# STM32_DDS.net
KiCad netlist of a schematic drawn in Altium Designer
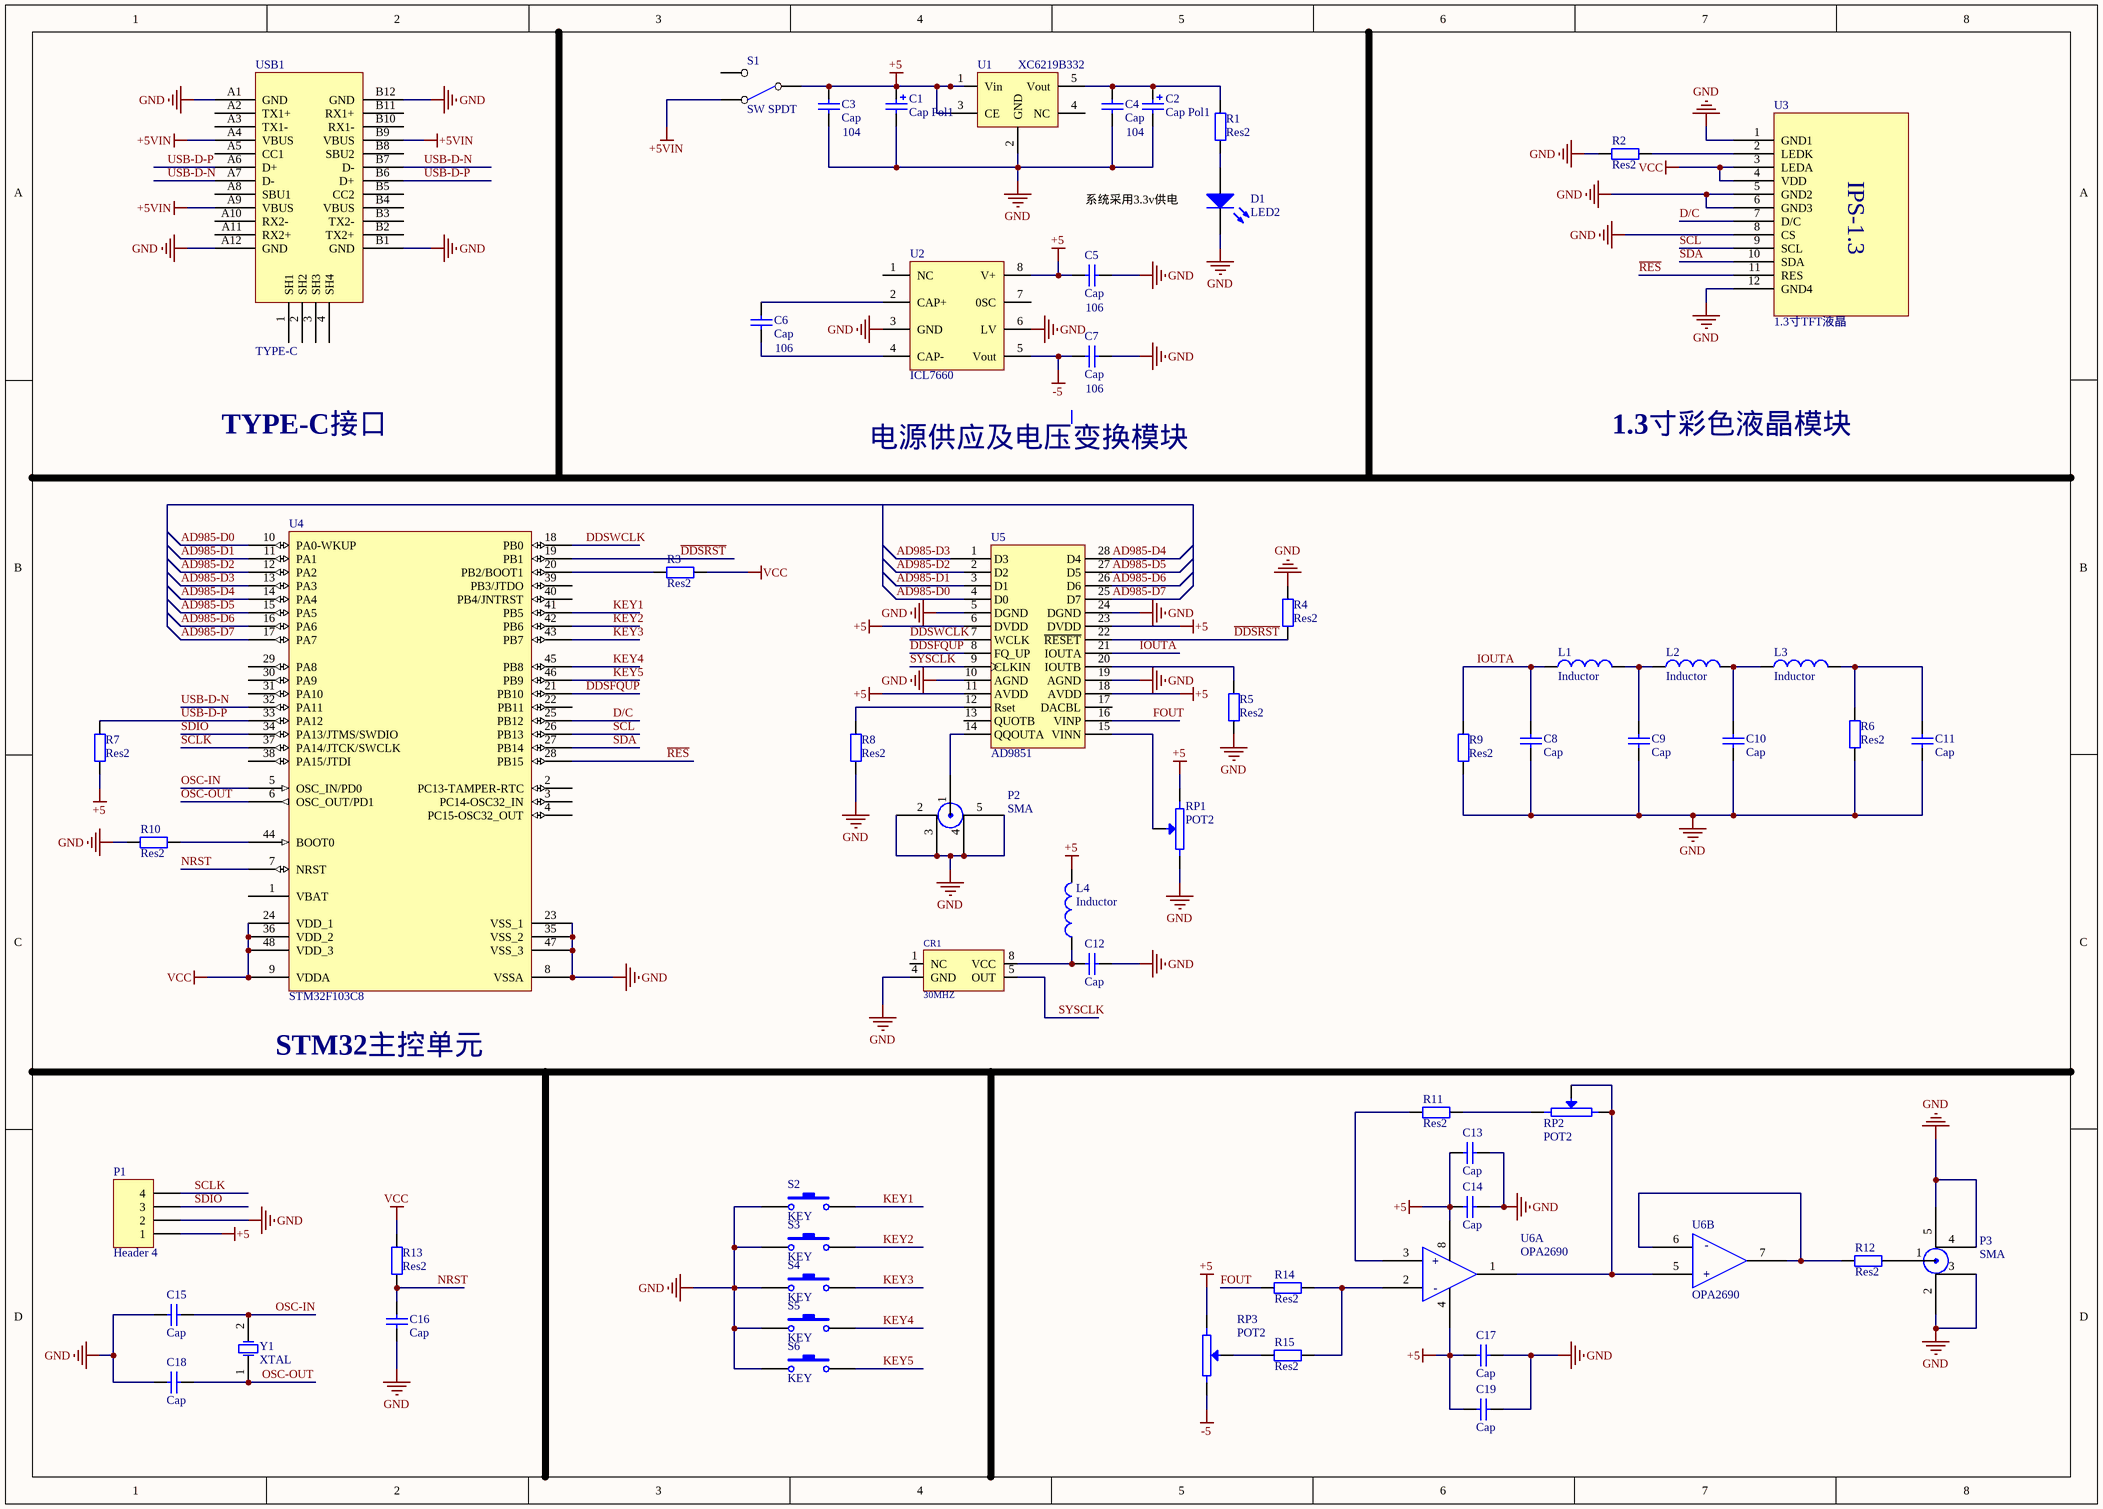
[diagram p0: 基于STM32的DDS信号源的设计实例.SchDoc]

(export (version "E")
  (design (tool "Eeschema 10.0.6"))
  (components
    (comp (ref "C1")
      (value "Cap Pol1")
      (footprint "C1210_N")
      (description "Polarized Capacitor (Radial)")
      (fields (field (name "PUBLISHER") "Altium Limited"))
      (libsource (lib "基于STM32的DDS信号源设计实例") (part "Cap Pol1"))
    )
    (comp (ref "C2")
      (value "Cap Pol1")
      (footprint "C1210_N")
      (description "Polarized Capacitor (Radial)")
      (fields (field (name "PUBLISHER") "Altium Limited"))
      (libsource (lib "基于STM32的DDS信号源设计实例") (part "Cap Pol1"))
    )
    (comp (ref "C3")
      (value "Cap")
      (footprint "C0805")
      (description "Capacitor")
      (fields (field (name "ALTIUM_VALUE") "104") (field (name "PUBLISHER") "Altium Limited"))
      (libsource (lib "基于STM32的DDS信号源设计实例") (part "Cap"))
    )
    (comp (ref "C4")
      (value "Cap")
      (footprint "C0805")
      (description "Capacitor")
      (fields (field (name "ALTIUM_VALUE") "104") (field (name "PUBLISHER") "Altium Limited"))
      (libsource (lib "基于STM32的DDS信号源设计实例") (part "Cap"))
    )
    (comp (ref "C5")
      (value "Cap")
      (footprint "C0805")
      (description "Capacitor")
      (fields (field (name "ALTIUM_VALUE") "106") (field (name "PUBLISHER") "Altium Limited"))
      (libsource (lib "基于STM32的DDS信号源设计实例") (part "Cap"))
    )
    (comp (ref "C6")
      (value "Cap")
      (footprint "C0805")
      (description "Capacitor")
      (fields (field (name "ALTIUM_VALUE") "106") (field (name "PUBLISHER") "Altium Limited"))
      (libsource (lib "基于STM32的DDS信号源设计实例") (part "Cap"))
    )
    (comp (ref "C7")
      (value "Cap")
      (footprint "C0805")
      (description "Capacitor")
      (fields (field (name "ALTIUM_VALUE") "106") (field (name "PUBLISHER") "Altium Limited"))
      (libsource (lib "基于STM32的DDS信号源设计实例") (part "Cap"))
    )
    (comp (ref "C8")
      (value "Cap")
      (footprint "C0805")
      (description "Capacitor")
      (fields (field (name "PUBLISHER") "Altium Limited"))
      (libsource (lib "基于STM32的DDS信号源设计实例") (part "Cap"))
    )
    (comp (ref "C9")
      (value "Cap")
      (footprint "C0805")
      (description "Capacitor")
      (fields (field (name "PUBLISHER") "Altium Limited"))
      (libsource (lib "基于STM32的DDS信号源设计实例") (part "Cap"))
    )
    (comp (ref "C10")
      (value "Cap")
      (footprint "C0805")
      (description "Capacitor")
      (fields (field (name "PUBLISHER") "Altium Limited"))
      (libsource (lib "基于STM32的DDS信号源设计实例") (part "Cap"))
    )
    (comp (ref "C11")
      (value "Cap")
      (footprint "C0805")
      (description "Capacitor")
      (fields (field (name "PUBLISHER") "Altium Limited"))
      (libsource (lib "基于STM32的DDS信号源设计实例") (part "Cap"))
    )
    (comp (ref "C12")
      (value "Cap")
      (footprint "C0805")
      (description "Capacitor")
      (fields (field (name "PUBLISHER") "Altium Limited"))
      (libsource (lib "基于STM32的DDS信号源设计实例") (part "Cap"))
    )
    (comp (ref "C13")
      (value "Cap")
      (footprint "C0805")
      (description "Capacitor")
      (fields (field (name "PUBLISHER") "Altium Limited"))
      (libsource (lib "基于STM32的DDS信号源设计实例") (part "Cap"))
    )
    (comp (ref "C14")
      (value "Cap")
      (footprint "C0805")
      (description "Capacitor")
      (fields (field (name "PUBLISHER") "Altium Limited"))
      (libsource (lib "基于STM32的DDS信号源设计实例") (part "Cap"))
    )
    (comp (ref "C15")
      (value "Cap")
      (footprint "C0805")
      (description "Capacitor")
      (fields (field (name "PUBLISHER") "Altium Limited"))
      (libsource (lib "基于STM32的DDS信号源设计实例") (part "Cap"))
    )
    (comp (ref "C16")
      (value "Cap")
      (footprint "C0805")
      (description "Capacitor")
      (fields (field (name "PUBLISHER") "Altium Limited"))
      (libsource (lib "基于STM32的DDS信号源设计实例") (part "Cap"))
    )
    (comp (ref "C17")
      (value "Cap")
      (footprint "C0805")
      (description "Capacitor")
      (fields (field (name "PUBLISHER") "Altium Limited"))
      (libsource (lib "基于STM32的DDS信号源设计实例") (part "Cap"))
    )
    (comp (ref "C18")
      (value "Cap")
      (footprint "C0805")
      (description "Capacitor")
      (fields (field (name "PUBLISHER") "Altium Limited"))
      (libsource (lib "基于STM32的DDS信号源设计实例") (part "Cap"))
    )
    (comp (ref "C19")
      (value "Cap")
      (footprint "C0805")
      (description "Capacitor")
      (fields (field (name "PUBLISHER") "Altium Limited"))
      (libsource (lib "基于STM32的DDS信号源设计实例") (part "Cap"))
    )
    (comp (ref "CR1")
      (value "30MHZ")
      (footprint "CRYSTAL-SMT-5X7")
      (libsource (lib "基于STM32的DDS信号源设计实例") (part "CRYSTAL-DIP8"))
    )
    (comp (ref "D1")
      (value "LED2")
      (footprint "D0805+")
      (description "Typical RED, GREEN, YELLOW, AMBER GaAs LED")
      (fields (field (name "PUBLISHER") "Altium Limited"))
      (libsource (lib "基于STM32的DDS信号源设计实例") (part "LED2"))
    )
    (comp (ref "L1")
      (value "Inductor")
      (footprint "6-0805_N")
      (fields (field (name "PUBLISHER") "Altium Limited"))
      (libsource (lib "基于STM32的DDS信号源设计实例") (part "Inductor"))
    )
    (comp (ref "L2")
      (value "Inductor")
      (footprint "6-0805_N")
      (fields (field (name "PUBLISHER") "Altium Limited"))
      (libsource (lib "基于STM32的DDS信号源设计实例") (part "Inductor"))
    )
    (comp (ref "L3")
      (value "Inductor")
      (footprint "6-0805_N")
      (fields (field (name "PUBLISHER") "Altium Limited"))
      (libsource (lib "基于STM32的DDS信号源设计实例") (part "Inductor"))
    )
    (comp (ref "L4")
      (value "Inductor")
      (footprint "6-0805_N")
      (fields (field (name "PUBLISHER") "Altium Limited"))
      (libsource (lib "基于STM32的DDS信号源设计实例") (part "Inductor"))
    )
    (comp (ref "P1")
      (value "Header 4")
      (footprint "HDR1X4")
      (description "Header, 4-Pin")
      (fields (field (name "PUBLISHER") "Altium Limited"))
      (libsource (lib "基于STM32的DDS信号源设计实例") (part "Header 4"))
    )
    (comp (ref "P2") (value "SMA") (footprint "SMA-KE") (libsource (lib "Schlib1") (part "SMA")))
    (comp (ref "P3") (value "SMA") (footprint "SMA-KE") (libsource (lib "原理图库") (part "SMA")))
    (comp (ref "R1")
      (value "Res2")
      (footprint "6-0805_N")
      (description "Resistor")
      (fields (field (name "PUBLISHER") "Altium Limited"))
      (libsource (lib "") (part "Res2_2"))
    )
    (comp (ref "R2")
      (value "Res2")
      (footprint "6-0805_N")
      (description "Resistor")
      (fields (field (name "PUBLISHER") "Altium Limited"))
      (libsource (lib "") (part "Res2_1"))
    )
    (comp (ref "R3")
      (value "Res2")
      (footprint "6-0805_N")
      (description "Resistor")
      (fields (field (name "PUBLISHER") "Altium Limited"))
      (libsource (lib "") (part "Res2_1"))
    )
    (comp (ref "R4")
      (value "Res2")
      (footprint "6-0805_N")
      (description "Resistor")
      (fields (field (name "PUBLISHER") "Altium Limited"))
      (libsource (lib "") (part "Res2_2"))
    )
    (comp (ref "R5")
      (value "Res2")
      (footprint "6-0805_N")
      (description "Resistor")
      (fields (field (name "PUBLISHER") "Altium Limited"))
      (libsource (lib "") (part "Res2_2"))
    )
    (comp (ref "R6")
      (value "Res2")
      (footprint "6-0805_N")
      (description "Resistor")
      (fields (field (name "PUBLISHER") "Altium Limited"))
      (libsource (lib "基于STM32的DDS信号源设计实例") (part "Res2"))
    )
    (comp (ref "R7")
      (value "Res2")
      (footprint "6-0805_N")
      (description "Resistor")
      (fields (field (name "PUBLISHER") "Altium Limited"))
      (libsource (lib "") (part "Res2_2"))
    )
    (comp (ref "R8")
      (value "Res2")
      (footprint "6-0805_N")
      (description "Resistor")
      (fields (field (name "PUBLISHER") "Altium Limited"))
      (libsource (lib "") (part "Res2_2"))
    )
    (comp (ref "R9")
      (value "Res2")
      (footprint "6-0805_N")
      (description "Resistor")
      (fields (field (name "PUBLISHER") "Altium Limited"))
      (libsource (lib "基于STM32的DDS信号源设计实例") (part "Res2"))
    )
    (comp (ref "R10")
      (value "Res2")
      (footprint "6-0805_N")
      (description "Resistor")
      (fields (field (name "PUBLISHER") "Altium Limited"))
      (libsource (lib "") (part "Res2_3"))
    )
    (comp (ref "R11")
      (value "Res2")
      (footprint "6-0805_N")
      (description "Resistor")
      (fields (field (name "PUBLISHER") "Altium Limited"))
      (libsource (lib "") (part "Res2_1"))
    )
    (comp (ref "R12")
      (value "Res2")
      (footprint "6-0805_N")
      (description "Resistor")
      (fields (field (name "PUBLISHER") "Altium Limited"))
      (libsource (lib "") (part "Res2_1"))
    )
    (comp (ref "R13")
      (value "Res2")
      (footprint "6-0805_N")
      (description "Resistor")
      (fields (field (name "PUBLISHER") "Altium Limited"))
      (libsource (lib "") (part "Res2_2"))
    )
    (comp (ref "R14")
      (value "Res2")
      (footprint "6-0805_N")
      (description "Resistor")
      (fields (field (name "PUBLISHER") "Altium Limited"))
      (libsource (lib "") (part "Res2_1"))
    )
    (comp (ref "R15")
      (value "Res2")
      (footprint "6-0805_N")
      (description "Resistor")
      (fields (field (name "PUBLISHER") "Altium Limited"))
      (libsource (lib "") (part "Res2_1"))
    )
    (comp (ref "RP1")
      (value "POT2")
      (footprint "VR7")
      (description "Potentiometer")
      (libsource (lib "基于STM32的DDS信号源设计实例") (part "POT2"))
    )
    (comp (ref "RP2")
      (value "POT2")
      (footprint "VR7")
      (description "Potentiometer")
      (libsource (lib "基于STM32的DDS信号源设计实例") (part "POT2"))
    )
    (comp (ref "RP3")
      (value "POT2")
      (footprint "VR7")
      (description "Potentiometer")
      (libsource (lib "基于STM32的DDS信号源设计实例") (part "POT2"))
    )
    (comp (ref "S1")
      (value "SW SPDT")
      (footprint "SW-SPDT-7P")
      (libsource (lib "基于STM32的DDS信号源设计实例") (part "SW SPDT"))
    )
    (comp (ref "S2")
      (value "KEY")
      (footprint "SW-MINI")
      (description "Switch")
      (fields (field (name "PUBLISHER") "Altium Limited"))
      (libsource (lib "基于STM32的DDS信号源设计实例") (part "SW-PB"))
    )
    (comp (ref "S3")
      (value "KEY")
      (footprint "SW-MINI")
      (description "Switch")
      (fields (field (name "PUBLISHER") "Altium Limited"))
      (libsource (lib "基于STM32的DDS信号源设计实例") (part "SW-PB"))
    )
    (comp (ref "S4")
      (value "KEY")
      (footprint "SW-MINI")
      (description "Switch")
      (fields (field (name "PUBLISHER") "Altium Limited"))
      (libsource (lib "基于STM32的DDS信号源设计实例") (part "SW-PB"))
    )
    (comp (ref "S5")
      (value "KEY")
      (footprint "SW-MINI")
      (description "Switch")
      (fields (field (name "PUBLISHER") "Altium Limited"))
      (libsource (lib "基于STM32的DDS信号源设计实例") (part "SW-PB"))
    )
    (comp (ref "S6")
      (value "KEY")
      (footprint "SW-MINI")
      (description "Switch")
      (fields (field (name "PUBLISHER") "Altium Limited"))
      (libsource (lib "基于STM32的DDS信号源设计实例") (part "SW-PB"))
    )
    (comp (ref "U1")
      (value "XC6219B332")
      (footprint "SOT23-5L")
      (libsource (lib "基于STM32的DDS信号源设计实例") (part "XC6219"))
    )
    (comp (ref "U2")
      (value "ICL7660")
      (footprint "SO8_N")
      (libsource (lib "基于STM32的DDS信号源设计实例") (part "ICL7660"))
    )
    (comp (ref "U3")
      (value "1.3寸TFT液晶")
      (footprint "1.3-TFT-TPS")
      (libsource (lib "基于STM32的DDS信号源设计实例") (part "1.3寸TFT液晶"))
    )
    (comp (ref "U4")
      (value "STM32F103C8")
      (footprint "TQFP-48")
      (description "Flaah:64/RAM:20/IO:36")
      (fields (field (name "版权归属") "源创客"))
      (libsource (lib "基于STM32的DDS信号源设计实例") (part "STM32F103C8"))
    )
    (comp (ref "U5") (value "AD9851") (footprint "TSSOP28") (libsource (lib "原理图库") (part "AD9851")))
    (comp (ref "U6") (value "OPA2690") (footprint "SO-8") (libsource (lib "原理图库") (part "OPA2690")))
    (comp (ref "USB1")
      (value "TYPE-C")
      (footprint "TYPE-C")
      (libsource (lib "基于STM32的DDS信号源设计实例") (part "TYPE-C"))
    )
    (comp (ref "Y1")
      (value "XTAL")
      (footprint "XTAL2")
      (description "Crystal Oscillator")
      (fields (field (name "PUBLISHER") "Altium Limited"))
      (libsource (lib "基于STM32的DDS信号源设计实例") (part "XTAL"))
    )
  )
  (nets
    (net (code "1") (name "+5") (class "Default")
      (node (ref "C1") (pin "1") (pinfunction "1_1") (pintype "passive"))
      (node (ref "C13") (pin "1") (pinfunction "1_1") (pintype "passive"))
      (node (ref "C14") (pin "1") (pinfunction "1_1") (pintype "passive"))
      (node (ref "C17") (pin "1") (pinfunction "1_1") (pintype "passive"))
      (node (ref "C19") (pin "1") (pinfunction "1_1") (pintype "passive"))
      (node (ref "C3") (pin "2") (pinfunction "2_2") (pintype "passive"))
      (node (ref "C5") (pin "2") (pinfunction "2_2") (pintype "passive"))
      (node (ref "L4") (pin "2") (pinfunction "2_2") (pintype "passive"))
      (node (ref "P1") (pin "1") (pinfunction "1_1") (pintype "passive"))
      (node (ref "R7") (pin "1") (pinfunction "1_1") (pintype "passive"))
      (node (ref "RP1") (pin "2") (pinfunction "2_2") (pintype "passive"))
      (node (ref "RP3") (pin "1") (pinfunction "1_1") (pintype "passive"))
      (node (ref "S1") (pin "2") (pinfunction "COMMON_2") (pintype "passive"))
      (node (ref "U1") (pin "1") (pinfunction "Vin_1") (pintype "passive"))
      (node (ref "U1") (pin "3") (pinfunction "CE_3") (pintype "passive"))
      (node (ref "U2") (pin "8") (pinfunction "V+_8") (pintype "passive"))
      (node (ref "U5") (pin "11") (pinfunction "AVDD_11") (pintype "passive"))
      (node (ref "U5") (pin "18") (pinfunction "AVDD_18") (pintype "passive"))
      (node (ref "U5") (pin "23") (pinfunction "DVDD_23") (pintype "passive"))
      (node (ref "U5") (pin "6") (pinfunction "DVDD_6") (pintype "passive"))
      (node (ref "U6") (pin "4") (pintype "passive"))
      (node (ref "U6") (pin "8") (pintype "passive"))
    )
    (net (code "2") (name "+5VIN") (class "Default")
      (node (ref "S1") (pin "1") (pinfunction "NC_1") (pintype "passive"))
      (node (ref "USB1") (pin "A4") (pinfunction "VBUS_A4") (pintype "passive"))
      (node (ref "USB1") (pin "A9") (pinfunction "VBUS_A9") (pintype "passive"))
      (node (ref "USB1") (pin "B9") (pinfunction "VBUS_B9") (pintype "passive"))
    )
    (net (code "3") (name "-5") (class "Default")
      (node (ref "C7") (pin "2") (pinfunction "2_2") (pintype "passive"))
      (node (ref "RP3") (pin "2") (pinfunction "2_2") (pintype "passive"))
      (node (ref "U2") (pin "5") (pinfunction "Vout_5") (pintype "passive"))
    )
    (net (code "5") (name "/AD985-D0") (class "Default")
      (node (ref "U4") (pin "10") (pinfunction "PA0-WKUP_10") (pintype "bidirectional"))
      (node (ref "U5") (pin "4") (pinfunction "D0_4") (pintype "passive"))
    )
    (net (code "6") (name "/AD985-D1") (class "Default")
      (node (ref "U4") (pin "11") (pinfunction "PA1_11") (pintype "bidirectional"))
      (node (ref "U5") (pin "3") (pinfunction "D1_3") (pintype "passive"))
    )
    (net (code "7") (name "/AD985-D2") (class "Default")
      (node (ref "U4") (pin "12") (pinfunction "PA2_12") (pintype "bidirectional"))
      (node (ref "U5") (pin "2") (pinfunction "D2_2") (pintype "passive"))
    )
    (net (code "8") (name "/AD985-D3") (class "Default")
      (node (ref "U4") (pin "13") (pinfunction "PA3_13") (pintype "bidirectional"))
      (node (ref "U5") (pin "1") (pinfunction "D3_1") (pintype "passive"))
    )
    (net (code "9") (name "/AD985-D4") (class "Default")
      (node (ref "U4") (pin "14") (pinfunction "PA4_14") (pintype "bidirectional"))
      (node (ref "U5") (pin "28") (pinfunction "D4_28") (pintype "passive"))
    )
    (net (code "10") (name "/AD985-D5") (class "Default")
      (node (ref "U4") (pin "15") (pinfunction "PA5_15") (pintype "bidirectional"))
      (node (ref "U5") (pin "27") (pinfunction "D5_27") (pintype "passive"))
    )
    (net (code "11") (name "/AD985-D6") (class "Default")
      (node (ref "U4") (pin "16") (pinfunction "PA6_16") (pintype "bidirectional"))
      (node (ref "U5") (pin "26") (pinfunction "D6_26") (pintype "passive"))
    )
    (net (code "12") (name "/AD985-D7") (class "Default")
      (node (ref "U4") (pin "17") (pinfunction "PA7_17") (pintype "bidirectional"))
      (node (ref "U5") (pin "25") (pinfunction "D7_25") (pintype "passive"))
    )
    (net (code "13") (name "/DDSFQUP") (class "Default")
      (node (ref "U4") (pin "21") (pinfunction "PB10_21") (pintype "bidirectional"))
      (node (ref "U5") (pin "8") (pinfunction "FQ_UP_8") (pintype "passive"))
    )
    (net (code "14") (name "/DDSWCLK") (class "Default")
      (node (ref "U4") (pin "18") (pinfunction "PB0_18") (pintype "bidirectional"))
      (node (ref "U5") (pin "7") (pinfunction "WCLK_7") (pintype "passive"))
    )
    (net (code "15") (name "/D{slash}C") (class "Default")
      (node (ref "U3") (pin "7") (pinfunction "D/C_7") (pintype "passive"))
      (node (ref "U4") (pin "25") (pinfunction "PB12_25") (pintype "bidirectional"))
    )
    (net (code "16") (name "/FOUT") (class "Default")
      (node (ref "R14") (pin "1") (pinfunction "1_1") (pintype "passive"))
      (node (ref "U5") (pin "16") (pinfunction "VINP_16") (pintype "passive"))
    )
    (net (code "17") (name "/IOUTA") (class "Default")
      (node (ref "C8") (pin "2") (pinfunction "2_2") (pintype "passive"))
      (node (ref "L1") (pin "1") (pinfunction "1_1") (pintype "passive"))
      (node (ref "R9") (pin "1") (pinfunction "1_1") (pintype "passive"))
      (node (ref "U5") (pin "21") (pinfunction "IOUTA_21") (pintype "passive"))
    )
    (net (code "18") (name "/KEY1") (class "Default")
      (node (ref "S2") (pin "2") (pinfunction "2_2") (pintype "passive"))
      (node (ref "U4") (pin "41") (pinfunction "PB5_41") (pintype "bidirectional"))
    )
    (net (code "19") (name "/KEY2") (class "Default")
      (node (ref "S3") (pin "2") (pinfunction "2_2") (pintype "passive"))
      (node (ref "U4") (pin "42") (pinfunction "PB6_42") (pintype "bidirectional"))
    )
    (net (code "20") (name "/KEY3") (class "Default")
      (node (ref "S4") (pin "2") (pinfunction "2_2") (pintype "passive"))
      (node (ref "U4") (pin "43") (pinfunction "PB7_43") (pintype "bidirectional"))
    )
    (net (code "21") (name "/KEY4") (class "Default")
      (node (ref "S5") (pin "2") (pinfunction "2_2") (pintype "passive"))
      (node (ref "U4") (pin "45") (pinfunction "PB8_45") (pintype "bidirectional"))
    )
    (net (code "22") (name "/KEY5") (class "Default")
      (node (ref "S6") (pin "2") (pinfunction "2_2") (pintype "passive"))
      (node (ref "U4") (pin "46") (pinfunction "PB9_46") (pintype "bidirectional"))
    )
    (net (code "23") (name "/NRST") (class "Default")
      (node (ref "C16") (pin "2") (pinfunction "2_2") (pintype "passive"))
      (node (ref "R13") (pin "1") (pinfunction "1_1") (pintype "passive"))
      (node (ref "U4") (pin "7") (pinfunction "NRST_7") (pintype "bidirectional"))
    )
    (net (code "24") (name "/OSC-IN") (class "Default")
      (node (ref "C15") (pin "2") (pinfunction "2_2") (pintype "passive"))
      (node (ref "U4") (pin "5") (pinfunction "OSC_IN/PD0_5") (pintype "input"))
      (node (ref "Y1") (pin "2") (pinfunction "OSC2_2") (pintype "passive"))
    )
    (net (code "25") (name "/OSC-OUT") (class "Default")
      (node (ref "C18") (pin "2") (pinfunction "2_2") (pintype "passive"))
      (node (ref "U4") (pin "6") (pinfunction "OSC_OUT/PD1_6") (pintype "output"))
      (node (ref "Y1") (pin "1") (pinfunction "OSC1_1") (pintype "passive"))
    )
    (net (code "26") (name "/SCL") (class "Default")
      (node (ref "U3") (pin "9") (pinfunction "SCL_9") (pintype "passive"))
      (node (ref "U4") (pin "26") (pinfunction "PB13_26") (pintype "bidirectional"))
    )
    (net (code "27") (name "/SCLK") (class "Default")
      (node (ref "P1") (pin "4") (pinfunction "4_4") (pintype "passive"))
      (node (ref "U4") (pin "37") (pinfunction "PA14/JTCK/SWCLK_37") (pintype "bidirectional"))
    )
    (net (code "28") (name "/SDA") (class "Default")
      (node (ref "U3") (pin "10") (pinfunction "SDA_10") (pintype "passive"))
      (node (ref "U4") (pin "27") (pinfunction "PB14_27") (pintype "bidirectional"))
    )
    (net (code "29") (name "/SDIO") (class "Default")
      (node (ref "P1") (pin "3") (pinfunction "3_3") (pintype "passive"))
      (node (ref "U4") (pin "34") (pinfunction "PA13/JTMS/SWDIO_34") (pintype "bidirectional"))
    )
    (net (code "30") (name "/SYSCLK") (class "Default")
      (node (ref "CR1") (pin "5") (pinfunction "OUT_5") (pintype "passive"))
      (node (ref "U5") (pin "9") (pinfunction "CLKIN_9") (pintype "passive"))
    )
    (net (code "31") (name "/USB-D-N") (class "Default")
      (node (ref "U4") (pin "32") (pinfunction "PA11_32") (pintype "bidirectional"))
      (node (ref "USB1") (pin "A7") (pinfunction "D-_A7") (pintype "passive"))
      (node (ref "USB1") (pin "B7") (pinfunction "D-_B7") (pintype "passive"))
    )
    (net (code "32") (name "/USB-D-P") (class "Default")
      (node (ref "R7") (pin "2") (pinfunction "2_2") (pintype "passive"))
      (node (ref "U4") (pin "33") (pinfunction "PA12_33") (pintype "bidirectional"))
      (node (ref "USB1") (pin "A6") (pinfunction "D+_A6") (pintype "passive"))
      (node (ref "USB1") (pin "B6") (pinfunction "D+_B6") (pintype "passive"))
    )
    (net (code "33") (name "/~{DDSRST}") (class "Default")
      (node (ref "R4") (pin "1") (pinfunction "1_1") (pintype "passive"))
      (node (ref "U4") (pin "19") (pinfunction "PB1_19") (pintype "bidirectional"))
      (node (ref "U5") (pin "22") (pinfunction "~{RESET}_22") (pintype "passive"))
    )
    (net (code "34") (name "/~{RES}") (class "Default")
      (node (ref "U3") (pin "11") (pinfunction "RES_11") (pintype "passive"))
      (node (ref "U4") (pin "28") (pinfunction "PB15_28") (pintype "bidirectional"))
    )
    (net (code "35") (name "GND") (class "Default")
      (node (ref "C1") (pin "2") (pinfunction "2_2") (pintype "passive"))
      (node (ref "C10") (pin "1") (pinfunction "1_1") (pintype "passive"))
      (node (ref "C11") (pin "1") (pinfunction "1_1") (pintype "passive"))
      (node (ref "C12") (pin "2") (pinfunction "2_2") (pintype "passive"))
      (node (ref "C13") (pin "2") (pinfunction "2_2") (pintype "passive"))
      (node (ref "C14") (pin "2") (pinfunction "2_2") (pintype "passive"))
      (node (ref "C15") (pin "1") (pinfunction "1_1") (pintype "passive"))
      (node (ref "C16") (pin "1") (pinfunction "1_1") (pintype "passive"))
      (node (ref "C17") (pin "2") (pinfunction "2_2") (pintype "passive"))
      (node (ref "C18") (pin "1") (pinfunction "1_1") (pintype "passive"))
      (node (ref "C19") (pin "2") (pinfunction "2_2") (pintype "passive"))
      (node (ref "C2") (pin "2") (pinfunction "2_2") (pintype "passive"))
      (node (ref "C3") (pin "1") (pinfunction "1_1") (pintype "passive"))
      (node (ref "C4") (pin "1") (pinfunction "1_1") (pintype "passive"))
      (node (ref "C5") (pin "1") (pinfunction "1_1") (pintype "passive"))
      (node (ref "C7") (pin "1") (pinfunction "1_1") (pintype "passive"))
      (node (ref "C8") (pin "1") (pinfunction "1_1") (pintype "passive"))
      (node (ref "C9") (pin "1") (pinfunction "1_1") (pintype "passive"))
      (node (ref "CR1") (pin "4") (pinfunction "GND_4") (pintype "passive"))
      (node (ref "D1") (pin "K") (pinfunction "K_K") (pintype "passive"))
      (node (ref "P1") (pin "2") (pinfunction "2_2") (pintype "passive"))
      (node (ref "P2") (pin "2") (pintype "passive"))
      (node (ref "P2") (pin "3") (pinfunction "3_3") (pintype "passive"))
      (node (ref "P2") (pin "4") (pinfunction "4_4") (pintype "passive"))
      (node (ref "P2") (pin "5") (pinfunction "5_5") (pintype "passive"))
      (node (ref "P3") (pin "2") (pintype "passive"))
      (node (ref "P3") (pin "3") (pinfunction "3_3") (pintype "passive"))
      (node (ref "P3") (pin "4") (pinfunction "4_4") (pintype "passive"))
      (node (ref "P3") (pin "5") (pinfunction "5_5") (pintype "passive"))
      (node (ref "R10") (pin "2") (pinfunction "2_2") (pintype "passive"))
      (node (ref "R2") (pin "1") (pinfunction "1_1") (pintype "passive"))
      (node (ref "R4") (pin "2") (pinfunction "2_2") (pintype "passive"))
      (node (ref "R5") (pin "1") (pinfunction "1_1") (pintype "passive"))
      (node (ref "R6") (pin "2") (pinfunction "2_2") (pintype "passive"))
      (node (ref "R8") (pin "1") (pinfunction "1_1") (pintype "passive"))
      (node (ref "R9") (pin "2") (pinfunction "2_2") (pintype "passive"))
      (node (ref "RP1") (pin "1") (pinfunction "1_1") (pintype "passive"))
      (node (ref "S2") (pin "1") (pinfunction "1_1") (pintype "passive"))
      (node (ref "S3") (pin "1") (pinfunction "1_1") (pintype "passive"))
      (node (ref "S4") (pin "1") (pinfunction "1_1") (pintype "passive"))
      (node (ref "S5") (pin "1") (pinfunction "1_1") (pintype "passive"))
      (node (ref "S6") (pin "1") (pinfunction "1_1") (pintype "passive"))
      (node (ref "U1") (pin "2") (pinfunction "GND_2") (pintype "power_in"))
      (node (ref "U2") (pin "3") (pinfunction "GND_3") (pintype "passive"))
      (node (ref "U2") (pin "6") (pinfunction "LV_6") (pintype "passive"))
      (node (ref "U3") (pin "1") (pinfunction "GND1_1") (pintype "passive"))
      (node (ref "U3") (pin "12") (pinfunction "GND4_12") (pintype "passive"))
      (node (ref "U3") (pin "5") (pinfunction "GND2_5") (pintype "passive"))
      (node (ref "U3") (pin "6") (pinfunction "GND3_6") (pintype "passive"))
      (node (ref "U3") (pin "8") (pinfunction "CS_8") (pintype "passive"))
      (node (ref "U4") (pin "23") (pinfunction "VSS_1_23") (pintype "power_in"))
      (node (ref "U4") (pin "35") (pinfunction "VSS_2_35") (pintype "power_in"))
      (node (ref "U4") (pin "47") (pinfunction "VSS_3_47") (pintype "power_in"))
      (node (ref "U4") (pin "8") (pinfunction "VSSA_8") (pintype "power_in"))
      (node (ref "U5") (pin "10") (pinfunction "AGND_10") (pintype "passive"))
      (node (ref "U5") (pin "19") (pinfunction "AGND_19") (pintype "passive"))
      (node (ref "U5") (pin "24") (pinfunction "DGND_24") (pintype "passive"))
      (node (ref "U5") (pin "5") (pinfunction "DGND_5") (pintype "passive"))
      (node (ref "USB1") (pin "A1") (pinfunction "GND_A1") (pintype "passive"))
      (node (ref "USB1") (pin "A12") (pinfunction "GND_A12") (pintype "passive"))
      (node (ref "USB1") (pin "B1") (pinfunction "GND_B1") (pintype "passive"))
      (node (ref "USB1") (pin "B12") (pinfunction "GND_B12") (pintype "passive"))
    )
    (net (code "36") (name "Net-(C9-Pad2)") (class "Default")
      (node (ref "C9") (pin "2") (pinfunction "2_2") (pintype "passive"))
      (node (ref "L1") (pin "2") (pinfunction "2_2") (pintype "passive"))
      (node (ref "L2") (pin "1") (pinfunction "1_1") (pintype "passive"))
    )
    (net (code "37") (name "Net-(C10-Pad2)") (class "Default")
      (node (ref "C10") (pin "2") (pinfunction "2_2") (pintype "passive"))
      (node (ref "L2") (pin "2") (pinfunction "2_2") (pintype "passive"))
      (node (ref "L3") (pin "1") (pinfunction "1_1") (pintype "passive"))
    )
    (net (code "38") (name "Net-(C11-Pad2)") (class "Default")
      (node (ref "C11") (pin "2") (pinfunction "2_2") (pintype "passive"))
      (node (ref "L3") (pin "2") (pinfunction "2_2") (pintype "passive"))
      (node (ref "R6") (pin "1") (pinfunction "1_1") (pintype "passive"))
    )
    (net (code "39") (name "Net-(CR1-VCC)") (class "Default")
      (node (ref "C12") (pin "1") (pinfunction "1_1") (pintype "passive"))
      (node (ref "CR1") (pin "8") (pinfunction "VCC_8") (pintype "passive"))
      (node (ref "L4") (pin "1") (pinfunction "1_1") (pintype "passive"))
    )
    (net (code "40") (name "Net-(D1-PadA)") (class "Default")
      (node (ref "D1") (pin "A") (pinfunction "A_A") (pintype "passive"))
      (node (ref "R1") (pin "1") (pinfunction "1_1") (pintype "passive"))
    )
    (net (code "41") (name "Net-(P3-Pad1)") (class "Default")
      (node (ref "P3") (pin "1") (pintype "passive"))
      (node (ref "R12") (pin "2") (pinfunction "2_2") (pintype "passive"))
    )
    (net (code "42") (name "Net-(R11-Pad1)") (class "Default")
      (node (ref "R11") (pin "1") (pinfunction "1_1") (pintype "passive"))
      (node (ref "U6") (pin "3") (pintype "passive"))
    )
    (net (code "43") (name "Net-(R11-Pad2)") (class "Default")
      (node (ref "R11") (pin "2") (pinfunction "2_2") (pintype "passive"))
      (node (ref "RP2") (pin "1") (pinfunction "1_1") (pintype "passive"))
    )
    (net (code "44") (name "Net-(R12-Pad1)") (class "Default")
      (node (ref "R12") (pin "1") (pinfunction "1_1") (pintype "passive"))
      (node (ref "U6") (pin "6") (pintype "passive"))
      (node (ref "U6") (pin "7") (pintype "passive"))
    )
    (net (code "45") (name "Net-(R14-Pad2)") (class "Default")
      (node (ref "R14") (pin "2") (pinfunction "2_2") (pintype "passive"))
      (node (ref "R15") (pin "2") (pinfunction "2_2") (pintype "passive"))
      (node (ref "U6") (pin "2") (pintype "passive"))
    )
    (net (code "46") (name "Net-(R15-Pad1)") (class "Default")
      (node (ref "R15") (pin "1") (pinfunction "1_1") (pintype "passive"))
      (node (ref "RP3") (pin "3") (pinfunction "3_3") (pintype "passive"))
    )
    (net (code "47") (name "Net-(RP2-Pad2)") (class "Default")
      (node (ref "RP2") (pin "2") (pinfunction "2_2") (pintype "passive"))
      (node (ref "RP2") (pin "3") (pinfunction "3_3") (pintype "passive"))
      (node (ref "U6") (pin "1") (pintype "passive"))
      (node (ref "U6") (pin "5") (pintype "passive"))
    )
    (net (code "48") (name "Net-(U1-Vout)") (class "Default")
      (node (ref "C2") (pin "1") (pinfunction "1_1") (pintype "passive"))
      (node (ref "C4") (pin "2") (pinfunction "2_2") (pintype "passive"))
      (node (ref "R1") (pin "2") (pinfunction "2_2") (pintype "passive"))
      (node (ref "U1") (pin "5") (pinfunction "Vout_5") (pintype "passive"))
    )
    (net (code "49") (name "Net-(U2-CAP+)") (class "Default")
      (node (ref "C6") (pin "2") (pinfunction "2_2") (pintype "passive"))
      (node (ref "U2") (pin "2") (pinfunction "CAP+_2") (pintype "passive"))
    )
    (net (code "50") (name "Net-(U2-CAP-)") (class "Default")
      (node (ref "C6") (pin "1") (pinfunction "1_1") (pintype "passive"))
      (node (ref "U2") (pin "4") (pinfunction "CAP-_4") (pintype "passive"))
    )
    (net (code "51") (name "Net-(U3-LEDK)") (class "Default")
      (node (ref "R2") (pin "2") (pinfunction "2_2") (pintype "passive"))
      (node (ref "U3") (pin "2") (pinfunction "LEDK_2") (pintype "passive"))
    )
    (net (code "52") (name "Net-(U4-BOOT0)") (class "Default")
      (node (ref "R10") (pin "1") (pinfunction "1_1") (pintype "passive"))
      (node (ref "U4") (pin "44") (pinfunction "BOOT0_44") (pintype "input"))
    )
    (net (code "53") (name "Net-(U4-PB2{slash}BOOT1)") (class "Default")
      (node (ref "R3") (pin "1") (pinfunction "1_1") (pintype "passive"))
      (node (ref "U4") (pin "20") (pinfunction "PB2/BOOT1_20") (pintype "bidirectional"))
    )
    (net (code "54") (name "Net-(U5-IOUTB)") (class "Default")
      (node (ref "R5") (pin "2") (pinfunction "2_2") (pintype "passive"))
      (node (ref "U5") (pin "20") (pinfunction "IOUTB_20") (pintype "passive"))
    )
    (net (code "55") (name "Net-(U5-QQOUTA)") (class "Default")
      (node (ref "P2") (pin "1") (pintype "passive"))
      (node (ref "U5") (pin "14") (pinfunction "QQOUTA_14") (pintype "passive"))
    )
    (net (code "56") (name "Net-(U5-Rset)") (class "Default")
      (node (ref "R8") (pin "2") (pinfunction "2_2") (pintype "passive"))
      (node (ref "U5") (pin "12") (pinfunction "Rset_12") (pintype "passive"))
    )
    (net (code "57") (name "Net-(U5-VINN)") (class "Default")
      (node (ref "RP1") (pin "3") (pinfunction "3_3") (pintype "passive"))
      (node (ref "U5") (pin "15") (pinfunction "VINN_15") (pintype "passive"))
    )
    (net (code "58") (name "VCC") (class "Default")
      (node (ref "R13") (pin "2") (pinfunction "2_2") (pintype "passive"))
      (node (ref "R3") (pin "2") (pinfunction "2_2") (pintype "passive"))
      (node (ref "U3") (pin "3") (pinfunction "LEDA_3") (pintype "passive"))
      (node (ref "U3") (pin "4") (pinfunction "VDD_4") (pintype "passive"))
      (node (ref "U4") (pin "24") (pinfunction "VDD_1_24") (pintype "power_in"))
      (node (ref "U4") (pin "36") (pinfunction "VDD_2_36") (pintype "power_in"))
      (node (ref "U4") (pin "48") (pinfunction "VDD_3_48") (pintype "power_in"))
      (node (ref "U4") (pin "9") (pinfunction "VDDA_9") (pintype "power_in"))
    )
    (net (code "59") (name "unconnected-(CR1-NC-Pad1)") (class "Default")
      (node (ref "CR1") (pin "1") (pinfunction "NC_1") (pintype "passive"))
    )
    (net (code "60") (name "unconnected-(S1-NO-Pad3)") (class "Default")
      (node (ref "S1") (pin "3") (pinfunction "NO_3") (pintype "passive"))
    )
    (net (code "61") (name "unconnected-(U1-NC-Pad4)") (class "Default")
      (node (ref "U1") (pin "4") (pinfunction "NC_4") (pintype "passive"))
    )
    (net (code "62") (name "unconnected-(U2-0SC-Pad7)") (class "Default")
      (node (ref "U2") (pin "7") (pinfunction "0SC_7") (pintype "passive"))
    )
    (net (code "63") (name "unconnected-(U2-NC-Pad1)") (class "Default")
      (node (ref "U2") (pin "1") (pinfunction "NC_1") (pintype "passive"))
    )
    (net (code "64") (name "unconnected-(U4-PA8-Pad29)") (class "Default")
      (node (ref "U4") (pin "29") (pinfunction "PA8_29") (pintype "bidirectional"))
    )
    (net (code "65") (name "unconnected-(U4-PA9-Pad30)") (class "Default")
      (node (ref "U4") (pin "30") (pinfunction "PA9_30") (pintype "bidirectional"))
    )
    (net (code "66") (name "unconnected-(U4-PA10-Pad31)") (class "Default")
      (node (ref "U4") (pin "31") (pinfunction "PA10_31") (pintype "bidirectional"))
    )
    (net (code "67") (name "unconnected-(U4-PA15{slash}JTDI-Pad38)") (class "Default")
      (node (ref "U4") (pin "38") (pinfunction "PA15/JTDI_38") (pintype "bidirectional"))
    )
    (net (code "68") (name "unconnected-(U4-PB3{slash}JTDO-Pad39)") (class "Default")
      (node (ref "U4") (pin "39") (pinfunction "PB3/JTDO_39") (pintype "bidirectional"))
    )
    (net (code "69") (name "unconnected-(U4-PB4{slash}JNTRST-Pad40)") (class "Default")
      (node (ref "U4") (pin "40") (pinfunction "PB4/JNTRST_40") (pintype "bidirectional"))
    )
    (net (code "70") (name "unconnected-(U4-PB11-Pad22)") (class "Default")
      (node (ref "U4") (pin "22") (pinfunction "PB11_22") (pintype "bidirectional"))
    )
    (net (code "71") (name "unconnected-(U4-PC13-TAMPER-RTC-Pad2)") (class "Default")
      (node (ref "U4") (pin "2") (pinfunction "PC13-TAMPER-RTC_2") (pintype "bidirectional"))
    )
    (net (code "72") (name "unconnected-(U4-PC14-OSC32_IN-Pad3)") (class "Default")
      (node (ref "U4") (pin "3") (pinfunction "PC14-OSC32_IN_3") (pintype "bidirectional"))
    )
    (net (code "73") (name "unconnected-(U4-PC15-OSC32_OUT-Pad4)") (class "Default")
      (node (ref "U4") (pin "4") (pinfunction "PC15-OSC32_OUT_4") (pintype "bidirectional"))
    )
    (net (code "74") (name "unconnected-(U4-VBAT-Pad1)") (class "Default")
      (node (ref "U4") (pin "1") (pinfunction "VBAT_1") (pintype "power_in"))
    )
    (net (code "75") (name "unconnected-(U5-DACBL-Pad17)") (class "Default")
      (node (ref "U5") (pin "17") (pinfunction "DACBL_17") (pintype "passive"))
    )
    (net (code "76") (name "unconnected-(U5-QUOTB-Pad13)") (class "Default")
      (node (ref "U5") (pin "13") (pinfunction "QUOTB_13") (pintype "passive"))
    )
    (net (code "77") (name "unconnected-(USB1-CC1-PadA5)") (class "Default")
      (node (ref "USB1") (pin "A5") (pinfunction "CC1_A5") (pintype "passive"))
    )
    (net (code "78") (name "unconnected-(USB1-CC2-PadB5)") (class "Default")
      (node (ref "USB1") (pin "B5") (pinfunction "CC2_B5") (pintype "passive"))
    )
    (net (code "79") (name "unconnected-(USB1-RX1+-PadB11)") (class "Default")
      (node (ref "USB1") (pin "B11") (pinfunction "RX1+_B11") (pintype "passive"))
    )
    (net (code "80") (name "unconnected-(USB1-RX1--PadB10)") (class "Default")
      (node (ref "USB1") (pin "B10") (pinfunction "RX1-_B10") (pintype "passive"))
    )
    (net (code "81") (name "unconnected-(USB1-RX2+-PadA11)") (class "Default")
      (node (ref "USB1") (pin "A11") (pinfunction "RX2+_A11") (pintype "passive"))
    )
    (net (code "82") (name "unconnected-(USB1-RX2--PadA10)") (class "Default")
      (node (ref "USB1") (pin "A10") (pinfunction "RX2-_A10") (pintype "passive"))
    )
    (net (code "83") (name "unconnected-(USB1-SBU1-PadA8)") (class "Default")
      (node (ref "USB1") (pin "A8") (pinfunction "SBU1_A8") (pintype "passive"))
    )
    (net (code "84") (name "unconnected-(USB1-SBU2-PadB8)") (class "Default")
      (node (ref "USB1") (pin "B8") (pinfunction "SBU2_B8") (pintype "passive"))
    )
    (net (code "85") (name "unconnected-(USB1-SH1-Pad1)") (class "Default")
      (node (ref "USB1") (pin "1") (pinfunction "SH1_1") (pintype "passive"))
    )
    (net (code "86") (name "unconnected-(USB1-SH2-Pad2)") (class "Default")
      (node (ref "USB1") (pin "2") (pinfunction "SH2_2") (pintype "passive"))
    )
    (net (code "87") (name "unconnected-(USB1-SH3-Pad3)") (class "Default")
      (node (ref "USB1") (pin "3") (pinfunction "SH3_3") (pintype "passive"))
    )
    (net (code "88") (name "unconnected-(USB1-SH4-Pad4)") (class "Default")
      (node (ref "USB1") (pin "4") (pinfunction "SH4_4") (pintype "passive"))
    )
    (net (code "89") (name "unconnected-(USB1-TX1+-PadA2)") (class "Default")
      (node (ref "USB1") (pin "A2") (pinfunction "TX1+_A2") (pintype "passive"))
    )
    (net (code "90") (name "unconnected-(USB1-TX1--PadA3)") (class "Default")
      (node (ref "USB1") (pin "A3") (pinfunction "TX1-_A3") (pintype "passive"))
    )
    (net (code "91") (name "unconnected-(USB1-TX2+-PadB2)") (class "Default")
      (node (ref "USB1") (pin "B2") (pinfunction "TX2+_B2") (pintype "passive"))
    )
    (net (code "92") (name "unconnected-(USB1-TX2--PadB3)") (class "Default")
      (node (ref "USB1") (pin "B3") (pinfunction "TX2-_B3") (pintype "passive"))
    )
    (net (code "93") (name "unconnected-(USB1-VBUS-PadB4)") (class "Default")
      (node (ref "USB1") (pin "B4") (pinfunction "VBUS_B4") (pintype "passive"))
    )
  )
)
